# Bus_UART.net
KiCad netlist of a schematic drawn in Altium Designer
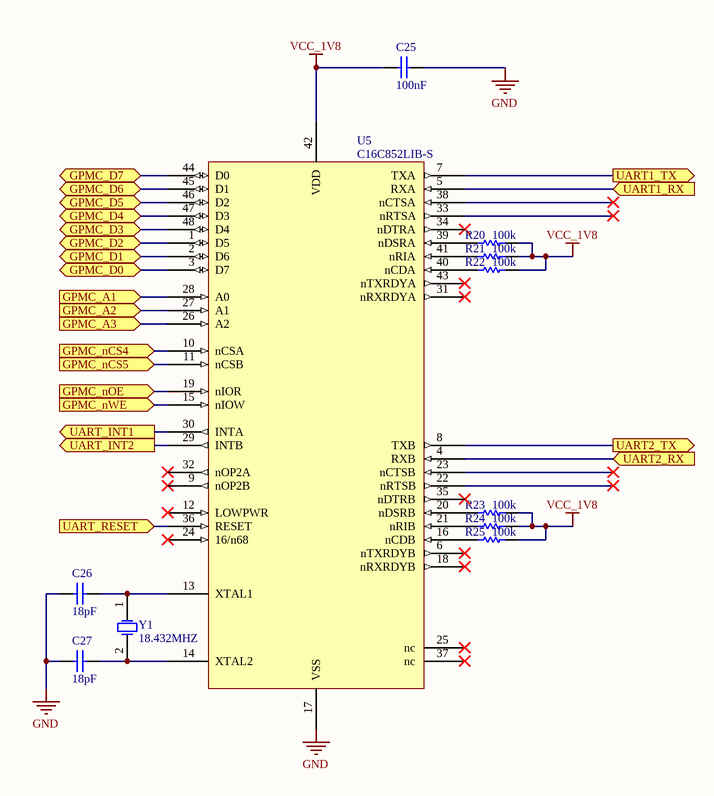
[diagram p0: Bus UART.SchDoc]

(export (version "E")
  (design (tool "Eeschema 10.0.6"))
  (components
    (comp (ref "C25")
      (value "100nF")
      (footprint "GRC PCB library:0603")
      (description "CAP CER .10UF 50V X5R 0603")
      (fields (field (name "MANUFACTURER") "Taiyo Yuden"))
      (libsource (lib "GRC sch library") (part "CP_100nF 0603"))
    )
    (comp (ref "C26")
      (value "18pF")
      (footprint "GRC PCB library:0603")
      (description "CAP CER 18PF 50V 5% C0G 0603")
      (fields (field (name "MANUFACTURER") "Murata Electronics North America"))
      (libsource (lib "GRC sch library") (part "CP_18pF 0603"))
    )
    (comp (ref "C27")
      (value "18pF")
      (footprint "GRC PCB library:0603")
      (description "CAP CER 18PF 50V 5% C0G 0603")
      (fields (field (name "MANUFACTURER") "Murata Electronics North America"))
      (libsource (lib "GRC sch library") (part "CP_18pF 0603"))
    )
    (comp (ref "R20")
      (value "100k")
      (footprint "GRC PCB library:0603")
      (description "RES 100K OHM 1/10W 1% 0603 SMD")
      (fields (field (name "MANUFACTURER") "Yageo"))
      (libsource (lib "GRC sch library") (part "RS_100k 0603"))
    )
    (comp (ref "R21")
      (value "100k")
      (footprint "GRC PCB library:0603")
      (description "RES 100K OHM 1/10W 1% 0603 SMD")
      (fields (field (name "MANUFACTURER") "Yageo"))
      (libsource (lib "GRC sch library") (part "RS_100k 0603"))
    )
    (comp (ref "R22")
      (value "100k")
      (footprint "GRC PCB library:0603")
      (description "RES 100K OHM 1/10W 1% 0603 SMD")
      (fields (field (name "MANUFACTURER") "Yageo"))
      (libsource (lib "GRC sch library") (part "RS_100k 0603"))
    )
    (comp (ref "R23")
      (value "100k")
      (footprint "GRC PCB library:0603")
      (description "RES 100K OHM 1/10W 1% 0603 SMD")
      (fields (field (name "MANUFACTURER") "Yageo"))
      (libsource (lib "GRC sch library") (part "RS_100k 0603"))
    )
    (comp (ref "R24")
      (value "100k")
      (footprint "GRC PCB library:0603")
      (description "RES 100K OHM 1/10W 1% 0603 SMD")
      (fields (field (name "MANUFACTURER") "Yageo"))
      (libsource (lib "GRC sch library") (part "RS_100k 0603"))
    )
    (comp (ref "R25")
      (value "100k")
      (footprint "GRC PCB library:0603")
      (description "RES 100K OHM 1/10W 1% 0603 SMD")
      (fields (field (name "MANUFACTURER") "Yageo"))
      (libsource (lib "GRC sch library") (part "RS_100k 0603"))
    )
    (comp (ref "U5")
      (value "C16C852LIB-S")
      (footprint "LQFP-48")
      (description "Dual high speed UARTs, bus connected")
      (libsource (lib "checked") (part "IC_SC16C852LIB-S"))
    )
    (comp (ref "Y1")
      (value "18.432MHZ")
      (footprint "GRC PCB library:ConWin_Xtal")
      (description "CRYSTAL 18.432MHZ LOW PRO SMD")
      (fields (field (name "MANUFACTURER") "Connor-Winfield"))
      (libsource (lib "GRC sch library") (part "XT_18.432MHZ"))
    )
  )
  (nets
    (net (code "1") (name "/GPMC_A1") (class "Default")
      (node (ref "U5") (pin "28") (pinfunction "A0_28") (pintype "input"))
    )
    (net (code "2") (name "/GPMC_A2") (class "Default")
      (node (ref "U5") (pin "27") (pinfunction "A1_27") (pintype "input"))
    )
    (net (code "3") (name "/GPMC_A3") (class "Default")
      (node (ref "U5") (pin "26") (pinfunction "A2_26") (pintype "input"))
    )
    (net (code "4") (name "/GPMC_D0") (class "Default")
      (node (ref "U5") (pin "3") (pinfunction "D7_3") (pintype "bidirectional"))
    )
    (net (code "5") (name "/GPMC_D1") (class "Default")
      (node (ref "U5") (pin "2") (pinfunction "D6_2") (pintype "bidirectional"))
    )
    (net (code "6") (name "/GPMC_D2") (class "Default")
      (node (ref "U5") (pin "1") (pinfunction "D5_1") (pintype "bidirectional"))
    )
    (net (code "7") (name "/GPMC_D3") (class "Default")
      (node (ref "U5") (pin "48") (pinfunction "D4_48") (pintype "bidirectional"))
    )
    (net (code "8") (name "/GPMC_D4") (class "Default")
      (node (ref "U5") (pin "47") (pinfunction "D3_47") (pintype "bidirectional"))
    )
    (net (code "9") (name "/GPMC_D5") (class "Default")
      (node (ref "U5") (pin "46") (pinfunction "D2_46") (pintype "bidirectional"))
    )
    (net (code "10") (name "/GPMC_D6") (class "Default")
      (node (ref "U5") (pin "45") (pinfunction "D1_45") (pintype "bidirectional"))
    )
    (net (code "11") (name "/GPMC_D7") (class "Default")
      (node (ref "U5") (pin "44") (pinfunction "D0_44") (pintype "bidirectional"))
    )
    (net (code "12") (name "/GPMC_nCS4") (class "Default")
      (node (ref "U5") (pin "10") (pinfunction "nCSA_10") (pintype "input"))
    )
    (net (code "13") (name "/GPMC_nCS5") (class "Default")
      (node (ref "U5") (pin "11") (pinfunction "nCSB_11") (pintype "input"))
    )
    (net (code "14") (name "/GPMC_nOE") (class "Default")
      (node (ref "U5") (pin "19") (pinfunction "nIOR_19") (pintype "input"))
    )
    (net (code "15") (name "/GPMC_nWE") (class "Default")
      (node (ref "U5") (pin "15") (pinfunction "nIOW_15") (pintype "input"))
    )
    (net (code "16") (name "/UART1_RX") (class "Default")
      (node (ref "U5") (pin "5") (pinfunction "RXA_5") (pintype "input"))
    )
    (net (code "17") (name "/UART1_TX") (class "Default")
      (node (ref "U5") (pin "7") (pinfunction "TXA_7") (pintype "output"))
    )
    (net (code "18") (name "/UART2_RX") (class "Default")
      (node (ref "U5") (pin "4") (pinfunction "RXB_4") (pintype "input"))
    )
    (net (code "19") (name "/UART2_TX") (class "Default")
      (node (ref "U5") (pin "8") (pinfunction "TXB_8") (pintype "output"))
    )
    (net (code "20") (name "/UART_INT1") (class "Default")
      (node (ref "U5") (pin "30") (pinfunction "INTA_30") (pintype "output"))
    )
    (net (code "21") (name "/UART_INT2") (class "Default")
      (node (ref "U5") (pin "29") (pinfunction "INTB_29") (pintype "output"))
    )
    (net (code "22") (name "/UART_RESET") (class "Default")
      (node (ref "U5") (pin "36") (pinfunction "RESET_36") (pintype "input"))
    )
    (net (code "23") (name "GND") (class "Default")
      (node (ref "C25") (pin "1") (pinfunction "1_1") (pintype "passive"))
      (node (ref "C26") (pin "1") (pinfunction "1_1") (pintype "passive"))
      (node (ref "C27") (pin "1") (pinfunction "1_1") (pintype "passive"))
      (node (ref "U5") (pin "17") (pinfunction "VSS_17") (pintype "power_in"))
    )
    (net (code "24") (name "Net-(U5-XTAL1)") (class "Default")
      (node (ref "C26") (pin "2") (pinfunction "2_2") (pintype "passive"))
      (node (ref "U5") (pin "13") (pinfunction "XTAL1_13") (pintype "power_in"))
      (node (ref "Y1") (pin "1") (pinfunction "OSC1_1") (pintype "passive"))
    )
    (net (code "25") (name "Net-(U5-XTAL2)") (class "Default")
      (node (ref "C27") (pin "2") (pinfunction "2_2") (pintype "passive"))
      (node (ref "U5") (pin "14") (pinfunction "XTAL2_14") (pintype "power_in"))
      (node (ref "Y1") (pin "2") (pinfunction "OSC2_2") (pintype "passive"))
    )
    (net (code "26") (name "Net-(U5-nCDA)") (class "Default")
      (node (ref "R22") (pin "1") (pinfunction "1_1") (pintype "passive"))
      (node (ref "U5") (pin "40") (pinfunction "nCDA_40") (pintype "input"))
    )
    (net (code "27") (name "Net-(U5-nCDB)") (class "Default")
      (node (ref "R25") (pin "1") (pinfunction "1_1") (pintype "passive"))
      (node (ref "U5") (pin "16") (pinfunction "nCDB_16") (pintype "input"))
    )
    (net (code "28") (name "Net-(U5-nDSRA)") (class "Default")
      (node (ref "R20") (pin "1") (pinfunction "1_1") (pintype "passive"))
      (node (ref "U5") (pin "39") (pinfunction "nDSRA_39") (pintype "input"))
    )
    (net (code "29") (name "Net-(U5-nDSRB)") (class "Default")
      (node (ref "R23") (pin "1") (pinfunction "1_1") (pintype "passive"))
      (node (ref "U5") (pin "20") (pinfunction "nDSRB_20") (pintype "input"))
    )
    (net (code "30") (name "Net-(U5-nRIA)") (class "Default")
      (node (ref "R21") (pin "1") (pinfunction "1_1") (pintype "passive"))
      (node (ref "U5") (pin "41") (pinfunction "nRIA_41") (pintype "input"))
    )
    (net (code "31") (name "Net-(U5-nRIB)") (class "Default")
      (node (ref "R24") (pin "1") (pinfunction "1_1") (pintype "passive"))
      (node (ref "U5") (pin "21") (pinfunction "nRIB_21") (pintype "input"))
    )
    (net (code "32") (name "VCC_1V8") (class "Default")
      (node (ref "C25") (pin "2") (pinfunction "2_2") (pintype "passive"))
      (node (ref "R20") (pin "2") (pinfunction "2_2") (pintype "passive"))
      (node (ref "R21") (pin "2") (pinfunction "2_2") (pintype "passive"))
      (node (ref "R22") (pin "2") (pinfunction "2_2") (pintype "passive"))
      (node (ref "R23") (pin "2") (pinfunction "2_2") (pintype "passive"))
      (node (ref "R24") (pin "2") (pinfunction "2_2") (pintype "passive"))
      (node (ref "R25") (pin "2") (pinfunction "2_2") (pintype "passive"))
      (node (ref "U5") (pin "42") (pinfunction "VDD_42") (pintype "power_in"))
    )
    (net (code "33") (name "unconnected-(U5-16{slash}n68-Pad24)") (class "Default")
      (node (ref "U5") (pin "24") (pinfunction "16/n68_24") (pintype "input+no_connect"))
    )
    (net (code "34") (name "unconnected-(U5-LOWPWR-Pad12)") (class "Default")
      (node (ref "U5") (pin "12") (pinfunction "LOWPWR_12") (pintype "input+no_connect"))
    )
    (net (code "35") (name "unconnected-(U5-nCTSA-Pad38)") (class "Default")
      (node (ref "U5") (pin "38") (pinfunction "nCTSA_38") (pintype "input+no_connect"))
    )
    (net (code "36") (name "unconnected-(U5-nCTSB-Pad23)") (class "Default")
      (node (ref "U5") (pin "23") (pinfunction "nCTSB_23") (pintype "input+no_connect"))
    )
    (net (code "37") (name "unconnected-(U5-nDTRA-Pad34)") (class "Default")
      (node (ref "U5") (pin "34") (pinfunction "nDTRA_34") (pintype "output+no_connect"))
    )
    (net (code "38") (name "unconnected-(U5-nDTRB-Pad35)") (class "Default")
      (node (ref "U5") (pin "35") (pinfunction "nDTRB_35") (pintype "output+no_connect"))
    )
    (net (code "39") (name "unconnected-(U5-nOP2A-Pad32)") (class "Default")
      (node (ref "U5") (pin "32") (pinfunction "nOP2A_32") (pintype "output+no_connect"))
    )
    (net (code "40") (name "unconnected-(U5-nOP2B-Pad9)") (class "Default")
      (node (ref "U5") (pin "9") (pinfunction "nOP2B_9") (pintype "output+no_connect"))
    )
    (net (code "41") (name "unconnected-(U5-nRTSA-Pad33)") (class "Default")
      (node (ref "U5") (pin "33") (pinfunction "nRTSA_33") (pintype "output+no_connect"))
    )
    (net (code "42") (name "unconnected-(U5-nRTSB-Pad22)") (class "Default")
      (node (ref "U5") (pin "22") (pinfunction "nRTSB_22") (pintype "output+no_connect"))
    )
    (net (code "43") (name "unconnected-(U5-nRXRDYA-Pad31)") (class "Default")
      (node (ref "U5") (pin "31") (pinfunction "nRXRDYA_31") (pintype "output+no_connect"))
    )
    (net (code "44") (name "unconnected-(U5-nRXRDYB-Pad18)") (class "Default")
      (node (ref "U5") (pin "18") (pinfunction "nRXRDYB_18") (pintype "output+no_connect"))
    )
    (net (code "45") (name "unconnected-(U5-nTXRDYA-Pad43)") (class "Default")
      (node (ref "U5") (pin "43") (pinfunction "nTXRDYA_43") (pintype "output+no_connect"))
    )
    (net (code "46") (name "unconnected-(U5-nTXRDYB-Pad6)") (class "Default")
      (node (ref "U5") (pin "6") (pinfunction "nTXRDYB_6") (pintype "output+no_connect"))
    )
    (net (code "47") (name "unconnected-(U5-nc-Pad25)") (class "Default")
      (node (ref "U5") (pin "25") (pinfunction "nc_25") (pintype "passive+no_connect"))
    )
    (net (code "48") (name "unconnected-(U5-nc-Pad37)") (class "Default")
      (node (ref "U5") (pin "37") (pinfunction "nc_37") (pintype "passive+no_connect"))
    )
  )
)
